# Sheet1.net
KiCad netlist of a schematic drawn in Altium Designer
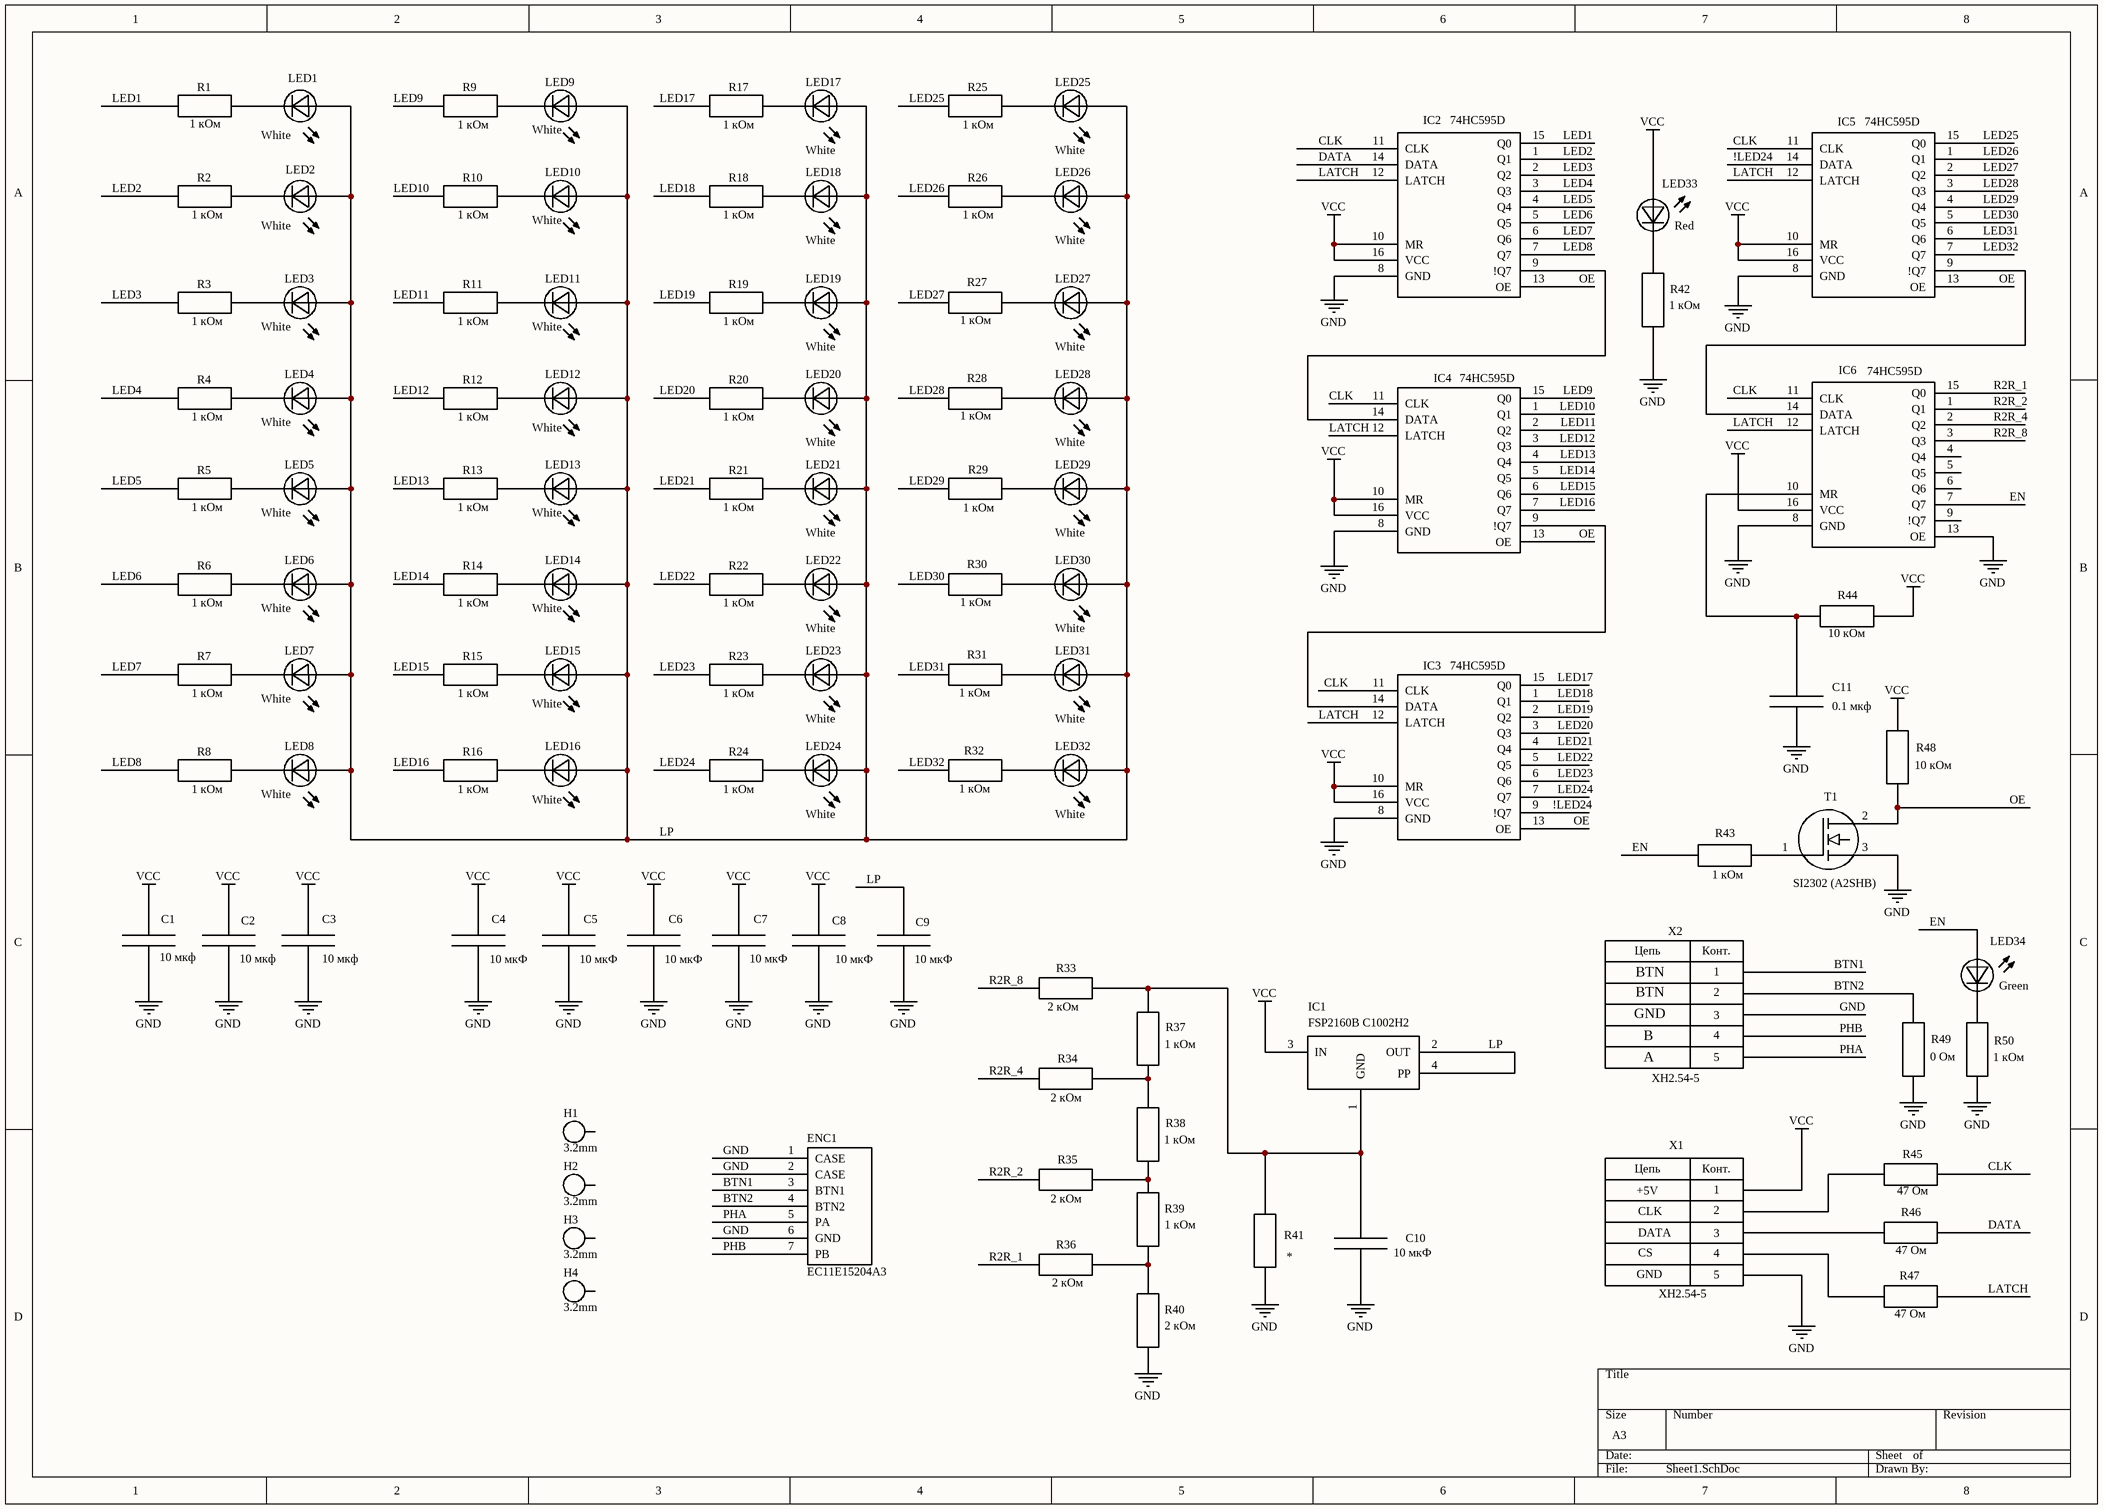
[diagram p0: Sheet1.SchDoc]

(export (version "E")
  (design (tool "Eeschema 10.0.6"))
  (components
    (comp (ref "C1")
      (value "10 мкф")
      (footprint "Конденсатор SMD Case 1206")
      (libsource (lib "S83") (part "Конденсатор"))
    )
    (comp (ref "C2")
      (value "10 мкф")
      (footprint "Конденсатор SMD Case 1206")
      (libsource (lib "S83") (part "Конденсатор"))
    )
    (comp (ref "C3")
      (value "10 мкф")
      (footprint "Конденсатор SMD Case 1206")
      (libsource (lib "S83") (part "Конденсатор"))
    )
    (comp (ref "C4")
      (value "10 мкФ")
      (footprint "Конденсатор SMD Case 1206")
      (libsource (lib "S83") (part "Конденсатор"))
    )
    (comp (ref "C5")
      (value "10 мкФ")
      (footprint "Конденсатор SMD Case 1206")
      (libsource (lib "S83") (part "Конденсатор"))
    )
    (comp (ref "C6")
      (value "10 мкФ")
      (footprint "Конденсатор SMD Case 1206")
      (libsource (lib "S83") (part "Конденсатор"))
    )
    (comp (ref "C7")
      (value "10 мкФ")
      (footprint "Конденсатор SMD Case 1206")
      (libsource (lib "S83") (part "Конденсатор"))
    )
    (comp (ref "C8")
      (value "10 мкФ")
      (footprint "Конденсатор SMD Case 1206")
      (libsource (lib "S83") (part "Конденсатор"))
    )
    (comp (ref "C9")
      (value "10 мкФ")
      (footprint "Конденсатор SMD Case 1206")
      (libsource (lib "S83") (part "Конденсатор"))
    )
    (comp (ref "C10")
      (value "10 мкФ")
      (footprint "Конденсатор SMD Case 1206")
      (libsource (lib "S83") (part "Конденсатор"))
    )
    (comp (ref "C11")
      (value "0.1 мкф")
      (footprint "Конденсатор SMD Case 1206")
      (libsource (lib "S83") (part "Конденсатор"))
    )
    (comp (ref "ENC1")
      (value "EC11E15204A3")
      (footprint "Encoder")
      (libsource (lib "S83") (part "Encoder_01"))
    )
    (comp (ref "H1")
      (value "3.2mm")
      (footprint "Отверстие 3,2")
      (libsource (lib "S83") (part "Отверстие монтажное"))
    )
    (comp (ref "H2")
      (value "3.2mm")
      (footprint "Отверстие 3,2")
      (libsource (lib "S83") (part "Отверстие монтажное"))
    )
    (comp (ref "H3")
      (value "3.2mm")
      (footprint "Отверстие 3,2")
      (libsource (lib "S83") (part "Отверстие монтажное"))
    )
    (comp (ref "H4")
      (value "3.2mm")
      (footprint "Отверстие 3,2")
      (libsource (lib "S83") (part "Отверстие монтажное"))
    )
    (comp (ref "IC1")
      (value "FSP2160B C1002H2")
      (footprint "SOT-223")
      (libsource (lib "S83_IC") (part "FSP2160B J1003H1"))
    )
    (comp (ref "IC2") (value "74HC595D") (footprint "SO-16") (libsource (lib "S83_IC") (part "74HC595D")))
    (comp (ref "IC3") (value "74HC595D") (footprint "SO-16") (libsource (lib "S83_IC") (part "74HC595D")))
    (comp (ref "IC4") (value "74HC595D") (footprint "SO-16") (libsource (lib "S83_IC") (part "74HC595D")))
    (comp (ref "IC5") (value "74HC595D") (footprint "SO-16") (libsource (lib "S83_IC") (part "74HC595D")))
    (comp (ref "IC6") (value "74HC595D") (footprint "SO-16") (libsource (lib "S83_IC") (part "74HC595D")))
    (comp (ref "LED1")
      (value "White")
      (footprint "Светодиод  5x2 mm")
      (libsource (lib "S83") (part "Светодиод"))
    )
    (comp (ref "LED2")
      (value "White")
      (footprint "Светодиод  5x2 mm")
      (libsource (lib "S83") (part "Светодиод"))
    )
    (comp (ref "LED3")
      (value "White")
      (footprint "Светодиод  5x2 mm")
      (libsource (lib "S83") (part "Светодиод"))
    )
    (comp (ref "LED4")
      (value "White")
      (footprint "Светодиод  5x2 mm")
      (libsource (lib "S83") (part "Светодиод"))
    )
    (comp (ref "LED5")
      (value "White")
      (footprint "Светодиод  5x2 mm")
      (libsource (lib "S83") (part "Светодиод"))
    )
    (comp (ref "LED6")
      (value "White")
      (footprint "Светодиод  5x2 mm")
      (libsource (lib "S83") (part "Светодиод"))
    )
    (comp (ref "LED7")
      (value "White")
      (footprint "Светодиод  5x2 mm")
      (libsource (lib "S83") (part "Светодиод"))
    )
    (comp (ref "LED8")
      (value "White")
      (footprint "Светодиод  5x2 mm")
      (libsource (lib "S83") (part "Светодиод"))
    )
    (comp (ref "LED9")
      (value "White")
      (footprint "Светодиод  5x2 mm")
      (libsource (lib "S83") (part "Светодиод"))
    )
    (comp (ref "LED10")
      (value "White")
      (footprint "Светодиод  5x2 mm")
      (libsource (lib "S83") (part "Светодиод"))
    )
    (comp (ref "LED11")
      (value "White")
      (footprint "Светодиод  5x2 mm")
      (libsource (lib "S83") (part "Светодиод"))
    )
    (comp (ref "LED12")
      (value "White")
      (footprint "Светодиод  5x2 mm")
      (libsource (lib "S83") (part "Светодиод"))
    )
    (comp (ref "LED13")
      (value "White")
      (footprint "Светодиод  5x2 mm")
      (libsource (lib "S83") (part "Светодиод"))
    )
    (comp (ref "LED14")
      (value "White")
      (footprint "Светодиод  5x2 mm")
      (libsource (lib "S83") (part "Светодиод"))
    )
    (comp (ref "LED15")
      (value "White")
      (footprint "Светодиод  5x2 mm")
      (libsource (lib "S83") (part "Светодиод"))
    )
    (comp (ref "LED16")
      (value "White")
      (footprint "Светодиод  5x2 mm")
      (libsource (lib "S83") (part "Светодиод"))
    )
    (comp (ref "LED17")
      (value "White")
      (footprint "Светодиод  5x2 mm")
      (libsource (lib "S83") (part "Светодиод"))
    )
    (comp (ref "LED18")
      (value "White")
      (footprint "Светодиод  5x2 mm")
      (libsource (lib "S83") (part "Светодиод"))
    )
    (comp (ref "LED19")
      (value "White")
      (footprint "Светодиод  5x2 mm")
      (libsource (lib "S83") (part "Светодиод"))
    )
    (comp (ref "LED20")
      (value "White")
      (footprint "Светодиод  5x2 mm")
      (libsource (lib "S83") (part "Светодиод"))
    )
    (comp (ref "LED21")
      (value "White")
      (footprint "Светодиод  5x2 mm")
      (libsource (lib "S83") (part "Светодиод"))
    )
    (comp (ref "LED22")
      (value "White")
      (footprint "Светодиод  5x2 mm")
      (libsource (lib "S83") (part "Светодиод"))
    )
    (comp (ref "LED23")
      (value "White")
      (footprint "Светодиод  5x2 mm")
      (libsource (lib "S83") (part "Светодиод"))
    )
    (comp (ref "LED24")
      (value "White")
      (footprint "Светодиод  5x2 mm")
      (libsource (lib "S83") (part "Светодиод"))
    )
    (comp (ref "LED25")
      (value "White")
      (footprint "Светодиод  5x2 mm")
      (libsource (lib "S83") (part "Светодиод"))
    )
    (comp (ref "LED26")
      (value "White")
      (footprint "Светодиод  5x2 mm")
      (libsource (lib "S83") (part "Светодиод"))
    )
    (comp (ref "LED27")
      (value "White")
      (footprint "Светодиод  5x2 mm")
      (libsource (lib "S83") (part "Светодиод"))
    )
    (comp (ref "LED28")
      (value "White")
      (footprint "Светодиод  5x2 mm")
      (libsource (lib "S83") (part "Светодиод"))
    )
    (comp (ref "LED29")
      (value "White")
      (footprint "Светодиод  5x2 mm")
      (libsource (lib "S83") (part "Светодиод"))
    )
    (comp (ref "LED30")
      (value "White")
      (footprint "Светодиод  5x2 mm")
      (libsource (lib "S83") (part "Светодиод"))
    )
    (comp (ref "LED31")
      (value "White")
      (footprint "Светодиод  5x2 mm")
      (libsource (lib "S83") (part "Светодиод"))
    )
    (comp (ref "LED32")
      (value "White")
      (footprint "Светодиод  5x2 mm")
      (libsource (lib "S83") (part "Светодиод"))
    )
    (comp (ref "LED33")
      (value "Red")
      (footprint "SMD 1206 Светодиод ВАЙТ")
      (libsource (lib "S83") (part "Светодиод"))
    )
    (comp (ref "LED34")
      (value "Green")
      (footprint "SMD 1206 Светодиод ВАЙТ")
      (libsource (lib "S83") (part "Светодиод"))
    )
    (comp (ref "R1")
      (value "1 кОм")
      (footprint "SMD 0805 Резистор")
      (libsource (lib "S83") (part "Резистор"))
    )
    (comp (ref "R2")
      (value "1 кОм")
      (footprint "SMD 0805 Резистор")
      (libsource (lib "S83") (part "Резистор"))
    )
    (comp (ref "R3")
      (value "1 кОм")
      (footprint "SMD 0805 Резистор")
      (libsource (lib "S83") (part "Резистор"))
    )
    (comp (ref "R4")
      (value "1 кОм")
      (footprint "SMD 0805 Резистор")
      (libsource (lib "S83") (part "Резистор"))
    )
    (comp (ref "R5")
      (value "1 кОм")
      (footprint "SMD 0805 Резистор")
      (libsource (lib "S83") (part "Резистор"))
    )
    (comp (ref "R6")
      (value "1 кОм")
      (footprint "SMD 0805 Резистор")
      (libsource (lib "S83") (part "Резистор"))
    )
    (comp (ref "R7")
      (value "1 кОм")
      (footprint "SMD 0805 Резистор")
      (libsource (lib "S83") (part "Резистор"))
    )
    (comp (ref "R8")
      (value "1 кОм")
      (footprint "SMD 0805 Резистор")
      (libsource (lib "S83") (part "Резистор"))
    )
    (comp (ref "R9")
      (value "1 кОм")
      (footprint "SMD 0805 Резистор")
      (libsource (lib "S83") (part "Резистор"))
    )
    (comp (ref "R10")
      (value "1 кОм")
      (footprint "SMD 0805 Резистор")
      (libsource (lib "S83") (part "Резистор"))
    )
    (comp (ref "R11")
      (value "1 кОм")
      (footprint "SMD 0805 Резистор")
      (libsource (lib "S83") (part "Резистор"))
    )
    (comp (ref "R12")
      (value "1 кОм")
      (footprint "SMD 0805 Резистор")
      (libsource (lib "S83") (part "Резистор"))
    )
    (comp (ref "R13")
      (value "1 кОм")
      (footprint "SMD 0805 Резистор")
      (libsource (lib "S83") (part "Резистор"))
    )
    (comp (ref "R14")
      (value "1 кОм")
      (footprint "SMD 0805 Резистор")
      (libsource (lib "S83") (part "Резистор"))
    )
    (comp (ref "R15")
      (value "1 кОм")
      (footprint "SMD 0805 Резистор")
      (libsource (lib "S83") (part "Резистор"))
    )
    (comp (ref "R16")
      (value "1 кОм")
      (footprint "SMD 0805 Резистор")
      (libsource (lib "S83") (part "Резистор"))
    )
    (comp (ref "R17")
      (value "1 кОм")
      (footprint "SMD 0805 Резистор")
      (libsource (lib "S83") (part "Резистор"))
    )
    (comp (ref "R18")
      (value "1 кОм")
      (footprint "SMD 0805 Резистор")
      (libsource (lib "S83") (part "Резистор"))
    )
    (comp (ref "R19")
      (value "1 кОм")
      (footprint "SMD 0805 Резистор")
      (libsource (lib "S83") (part "Резистор"))
    )
    (comp (ref "R20")
      (value "1 кОм")
      (footprint "SMD 0805 Резистор")
      (libsource (lib "S83") (part "Резистор"))
    )
    (comp (ref "R21")
      (value "1 кОм")
      (footprint "SMD 0805 Резистор")
      (libsource (lib "S83") (part "Резистор"))
    )
    (comp (ref "R22")
      (value "1 кОм")
      (footprint "SMD 0805 Резистор")
      (libsource (lib "S83") (part "Резистор"))
    )
    (comp (ref "R23")
      (value "1 кОм")
      (footprint "SMD 0805 Резистор")
      (libsource (lib "S83") (part "Резистор"))
    )
    (comp (ref "R24")
      (value "1 кОм")
      (footprint "SMD 0805 Резистор")
      (libsource (lib "S83") (part "Резистор"))
    )
    (comp (ref "R25")
      (value "1 кОм")
      (footprint "SMD 0805 Резистор")
      (libsource (lib "S83") (part "Резистор"))
    )
    (comp (ref "R26")
      (value "1 кОм")
      (footprint "SMD 0805 Резистор")
      (libsource (lib "S83") (part "Резистор"))
    )
    (comp (ref "R27")
      (value "1 кОм")
      (footprint "SMD 0805 Резистор")
      (libsource (lib "S83") (part "Резистор"))
    )
    (comp (ref "R28")
      (value "1 кОм")
      (footprint "SMD 0805 Резистор")
      (libsource (lib "S83") (part "Резистор"))
    )
    (comp (ref "R29")
      (value "1 кОм")
      (footprint "SMD 0805 Резистор")
      (libsource (lib "S83") (part "Резистор"))
    )
    (comp (ref "R30")
      (value "1 кОм")
      (footprint "SMD 0805 Резистор")
      (libsource (lib "S83") (part "Резистор"))
    )
    (comp (ref "R31")
      (value "1 кОм")
      (footprint "SMD 0805 Резистор")
      (libsource (lib "S83") (part "Резистор"))
    )
    (comp (ref "R32")
      (value "1 кОм")
      (footprint "SMD 0805 Резистор")
      (libsource (lib "S83") (part "Резистор"))
    )
    (comp (ref "R33")
      (value "2 кОм")
      (footprint "SMD 0805 Резистор")
      (libsource (lib "S83") (part "Резистор"))
    )
    (comp (ref "R34")
      (value "2 кОм")
      (footprint "SMD 0805 Резистор")
      (libsource (lib "S83") (part "Резистор"))
    )
    (comp (ref "R35")
      (value "2 кОм")
      (footprint "SMD 0805 Резистор")
      (libsource (lib "S83") (part "Резистор"))
    )
    (comp (ref "R36")
      (value "2 кОм")
      (footprint "SMD 0805 Резистор")
      (libsource (lib "S83") (part "Резистор"))
    )
    (comp (ref "R37")
      (value "1 кОм")
      (footprint "SMD 0805 Резистор")
      (libsource (lib "S83") (part "Резистор"))
    )
    (comp (ref "R38")
      (value "1 кОм")
      (footprint "SMD 0805 Резистор")
      (libsource (lib "S83") (part "Резистор"))
    )
    (comp (ref "R39")
      (value "1 кОм")
      (footprint "SMD 0805 Резистор")
      (libsource (lib "S83") (part "Резистор"))
    )
    (comp (ref "R40")
      (value "2 кОм")
      (footprint "SMD 0805 Резистор")
      (libsource (lib "S83") (part "Резистор"))
    )
    (comp (ref "R41") (value "*") (footprint "SMD 0805 Резистор") (libsource (lib "S83") (part "Резистор")))
    (comp (ref "R42")
      (value "1 кОм")
      (footprint "SMD 0805 Резистор")
      (libsource (lib "S83") (part "Резистор"))
    )
    (comp (ref "R43")
      (value "1 кОм")
      (footprint "SMD 0805 Резистор")
      (libsource (lib "S83") (part "Резистор"))
    )
    (comp (ref "R44")
      (value "10 кОм")
      (footprint "SMD 0805 Резистор")
      (libsource (lib "S83") (part "Резистор"))
    )
    (comp (ref "R45")
      (value "47 Ом")
      (footprint "SMD 0805 Резистор")
      (libsource (lib "S83") (part "Резистор"))
    )
    (comp (ref "R46")
      (value "47 Ом")
      (footprint "SMD 0805 Резистор")
      (libsource (lib "S83") (part "Резистор"))
    )
    (comp (ref "R47")
      (value "47 Ом")
      (footprint "SMD 0805 Резистор")
      (libsource (lib "S83") (part "Резистор"))
    )
    (comp (ref "R48")
      (value "10 кОм")
      (footprint "SMD 0805 Резистор")
      (libsource (lib "S83") (part "Резистор"))
    )
    (comp (ref "R49")
      (value "0 Ом")
      (footprint "SMD 0805 Резистор")
      (libsource (lib "S83") (part "Резистор"))
    )
    (comp (ref "R50")
      (value "1 кОм")
      (footprint "SMD 0805 Резистор")
      (libsource (lib "S83") (part "Резистор"))
    )
    (comp (ref "T1")
      (value "SI2302 (A2SHB)")
      (footprint "SMD SOT-23 Транзистор 3 pin")
      (libsource (lib "S83") (part "Транзистор MOSFET N-конал (как n-p-n)"))
    )
    (comp (ref "X1")
      (value "XH2.54-5")
      (footprint "(1x5)pin XH 2.54 Header")
      (libsource (lib "S83_connectors") (part "(1x5) pin 2.54 Header"))
    )
    (comp (ref "X2")
      (value "XH2.54-5")
      (footprint "(1x5)pin XH 2.54 Header")
      (libsource (lib "S83_connectors") (part "(1x5) pin 2.54 Header"))
    )
  )
  (nets
    (net (code "1") (name "/!LED24") (class "Default")
      (node (ref "IC3") (pin "9") (pinfunction "!Q7_9") (pintype "passive"))
      (node (ref "IC5") (pin "14") (pinfunction "DATA_14") (pintype "passive"))
    )
    (net (code "2") (name "/BTN1") (class "Default")
      (node (ref "ENC1") (pin "3") (pinfunction "BTN1_3") (pintype "passive"))
      (node (ref "X2") (pin "1") (pinfunction "1_1") (pintype "passive"))
    )
    (net (code "3") (name "/BTN2") (class "Default")
      (node (ref "ENC1") (pin "4") (pinfunction "BTN2_4") (pintype "passive"))
      (node (ref "R49") (pin "2") (pinfunction "right_2") (pintype "passive"))
      (node (ref "X2") (pin "2") (pinfunction "2_2") (pintype "passive"))
    )
    (net (code "4") (name "/CLK") (class "Default")
      (node (ref "IC2") (pin "11") (pinfunction "CLK_11") (pintype "passive"))
      (node (ref "IC3") (pin "11") (pinfunction "CLK_11") (pintype "passive"))
      (node (ref "IC4") (pin "11") (pinfunction "CLK_11") (pintype "passive"))
      (node (ref "IC5") (pin "11") (pinfunction "CLK_11") (pintype "passive"))
      (node (ref "IC6") (pin "11") (pinfunction "CLK_11") (pintype "passive"))
      (node (ref "R45") (pin "1") (pinfunction "left_1") (pintype "passive"))
    )
    (net (code "5") (name "/DATA") (class "Default")
      (node (ref "IC2") (pin "14") (pinfunction "DATA_14") (pintype "passive"))
      (node (ref "R46") (pin "1") (pinfunction "left_1") (pintype "passive"))
    )
    (net (code "6") (name "/EN") (class "Default")
      (node (ref "IC6") (pin "7") (pinfunction "Q7_7") (pintype "passive"))
      (node (ref "LED34") (pin "1") (pinfunction "А_1") (pintype "passive"))
      (node (ref "R43") (pin "2") (pinfunction "right_2") (pintype "passive"))
    )
    (net (code "7") (name "/LATCH") (class "Default")
      (node (ref "IC2") (pin "12") (pinfunction "LATCH_12") (pintype "passive"))
      (node (ref "IC3") (pin "12") (pinfunction "LATCH_12") (pintype "passive"))
      (node (ref "IC4") (pin "12") (pinfunction "LATCH_12") (pintype "passive"))
      (node (ref "IC5") (pin "12") (pinfunction "LATCH_12") (pintype "passive"))
      (node (ref "IC6") (pin "12") (pinfunction "LATCH_12") (pintype "passive"))
      (node (ref "R47") (pin "1") (pinfunction "left_1") (pintype "passive"))
    )
    (net (code "8") (name "/LED1") (class "Default")
      (node (ref "IC2") (pin "15") (pinfunction "Q0_15") (pintype "passive"))
      (node (ref "R1") (pin "1") (pinfunction "left_1") (pintype "passive"))
    )
    (net (code "9") (name "/LED2") (class "Default")
      (node (ref "IC2") (pin "1") (pinfunction "Q1_1") (pintype "passive"))
      (node (ref "R2") (pin "1") (pinfunction "left_1") (pintype "passive"))
    )
    (net (code "10") (name "/LED3") (class "Default")
      (node (ref "IC2") (pin "2") (pinfunction "Q2_2") (pintype "passive"))
      (node (ref "R3") (pin "1") (pinfunction "left_1") (pintype "passive"))
    )
    (net (code "11") (name "/LED4") (class "Default")
      (node (ref "IC2") (pin "3") (pinfunction "Q3_3") (pintype "passive"))
      (node (ref "R4") (pin "1") (pinfunction "left_1") (pintype "passive"))
    )
    (net (code "12") (name "/LED5") (class "Default")
      (node (ref "IC2") (pin "4") (pinfunction "Q4_4") (pintype "passive"))
      (node (ref "R5") (pin "1") (pinfunction "left_1") (pintype "passive"))
    )
    (net (code "13") (name "/LED6") (class "Default")
      (node (ref "IC2") (pin "5") (pinfunction "Q5_5") (pintype "passive"))
      (node (ref "R6") (pin "1") (pinfunction "left_1") (pintype "passive"))
    )
    (net (code "14") (name "/LED7") (class "Default")
      (node (ref "IC2") (pin "6") (pinfunction "Q6_6") (pintype "passive"))
      (node (ref "R7") (pin "1") (pinfunction "left_1") (pintype "passive"))
    )
    (net (code "15") (name "/LED8") (class "Default")
      (node (ref "IC2") (pin "7") (pinfunction "Q7_7") (pintype "passive"))
      (node (ref "R8") (pin "1") (pinfunction "left_1") (pintype "passive"))
    )
    (net (code "16") (name "/LED9") (class "Default")
      (node (ref "IC4") (pin "15") (pinfunction "Q0_15") (pintype "passive"))
      (node (ref "R9") (pin "1") (pinfunction "left_1") (pintype "passive"))
    )
    (net (code "17") (name "/LED10") (class "Default")
      (node (ref "IC4") (pin "1") (pinfunction "Q1_1") (pintype "passive"))
      (node (ref "R10") (pin "1") (pinfunction "left_1") (pintype "passive"))
    )
    (net (code "18") (name "/LED11") (class "Default")
      (node (ref "IC4") (pin "2") (pinfunction "Q2_2") (pintype "passive"))
      (node (ref "R11") (pin "1") (pinfunction "left_1") (pintype "passive"))
    )
    (net (code "19") (name "/LED12") (class "Default")
      (node (ref "IC4") (pin "3") (pinfunction "Q3_3") (pintype "passive"))
      (node (ref "R12") (pin "1") (pinfunction "left_1") (pintype "passive"))
    )
    (net (code "20") (name "/LED13") (class "Default")
      (node (ref "IC4") (pin "4") (pinfunction "Q4_4") (pintype "passive"))
      (node (ref "R13") (pin "1") (pinfunction "left_1") (pintype "passive"))
    )
    (net (code "21") (name "/LED14") (class "Default")
      (node (ref "IC4") (pin "5") (pinfunction "Q5_5") (pintype "passive"))
      (node (ref "R14") (pin "1") (pinfunction "left_1") (pintype "passive"))
    )
    (net (code "22") (name "/LED15") (class "Default")
      (node (ref "IC4") (pin "6") (pinfunction "Q6_6") (pintype "passive"))
      (node (ref "R15") (pin "1") (pinfunction "left_1") (pintype "passive"))
    )
    (net (code "23") (name "/LED16") (class "Default")
      (node (ref "IC4") (pin "7") (pinfunction "Q7_7") (pintype "passive"))
      (node (ref "R16") (pin "1") (pinfunction "left_1") (pintype "passive"))
    )
    (net (code "24") (name "/LED17") (class "Default")
      (node (ref "IC3") (pin "15") (pinfunction "Q0_15") (pintype "passive"))
      (node (ref "R17") (pin "1") (pinfunction "left_1") (pintype "passive"))
    )
    (net (code "25") (name "/LED18") (class "Default")
      (node (ref "IC3") (pin "1") (pinfunction "Q1_1") (pintype "passive"))
      (node (ref "R18") (pin "1") (pinfunction "left_1") (pintype "passive"))
    )
    (net (code "26") (name "/LED19") (class "Default")
      (node (ref "IC3") (pin "2") (pinfunction "Q2_2") (pintype "passive"))
      (node (ref "R19") (pin "1") (pinfunction "left_1") (pintype "passive"))
    )
    (net (code "27") (name "/LED20") (class "Default")
      (node (ref "IC3") (pin "3") (pinfunction "Q3_3") (pintype "passive"))
      (node (ref "R20") (pin "1") (pinfunction "left_1") (pintype "passive"))
    )
    (net (code "28") (name "/LED21") (class "Default")
      (node (ref "IC3") (pin "4") (pinfunction "Q4_4") (pintype "passive"))
      (node (ref "R21") (pin "1") (pinfunction "left_1") (pintype "passive"))
    )
    (net (code "29") (name "/LED22") (class "Default")
      (node (ref "IC3") (pin "5") (pinfunction "Q5_5") (pintype "passive"))
      (node (ref "R22") (pin "1") (pinfunction "left_1") (pintype "passive"))
    )
    (net (code "30") (name "/LED23") (class "Default")
      (node (ref "IC3") (pin "6") (pinfunction "Q6_6") (pintype "passive"))
      (node (ref "R23") (pin "1") (pinfunction "left_1") (pintype "passive"))
    )
    (net (code "31") (name "/LED24") (class "Default")
      (node (ref "IC3") (pin "7") (pinfunction "Q7_7") (pintype "passive"))
      (node (ref "R24") (pin "1") (pinfunction "left_1") (pintype "passive"))
    )
    (net (code "32") (name "/LED25") (class "Default")
      (node (ref "IC5") (pin "15") (pinfunction "Q0_15") (pintype "passive"))
      (node (ref "R25") (pin "1") (pinfunction "left_1") (pintype "passive"))
    )
    (net (code "33") (name "/LED26") (class "Default")
      (node (ref "IC5") (pin "1") (pinfunction "Q1_1") (pintype "passive"))
      (node (ref "R26") (pin "1") (pinfunction "left_1") (pintype "passive"))
    )
    (net (code "34") (name "/LED27") (class "Default")
      (node (ref "IC5") (pin "2") (pinfunction "Q2_2") (pintype "passive"))
      (node (ref "R27") (pin "1") (pinfunction "left_1") (pintype "passive"))
    )
    (net (code "35") (name "/LED28") (class "Default")
      (node (ref "IC5") (pin "3") (pinfunction "Q3_3") (pintype "passive"))
      (node (ref "R28") (pin "1") (pinfunction "left_1") (pintype "passive"))
    )
    (net (code "36") (name "/LED29") (class "Default")
      (node (ref "IC5") (pin "4") (pinfunction "Q4_4") (pintype "passive"))
      (node (ref "R29") (pin "1") (pinfunction "left_1") (pintype "passive"))
    )
    (net (code "37") (name "/LED30") (class "Default")
      (node (ref "IC5") (pin "5") (pinfunction "Q5_5") (pintype "passive"))
      (node (ref "R30") (pin "1") (pinfunction "left_1") (pintype "passive"))
    )
    (net (code "38") (name "/LED31") (class "Default")
      (node (ref "IC5") (pin "6") (pinfunction "Q6_6") (pintype "passive"))
      (node (ref "R31") (pin "1") (pinfunction "left_1") (pintype "passive"))
    )
    (net (code "39") (name "/LED32") (class "Default")
      (node (ref "IC5") (pin "7") (pinfunction "Q7_7") (pintype "passive"))
      (node (ref "R32") (pin "1") (pinfunction "left_1") (pintype "passive"))
    )
    (net (code "40") (name "/LP") (class "Default")
      (node (ref "C9") (pin "1") (pinfunction "+_1") (pintype "passive"))
      (node (ref "IC1") (pin "2") (pinfunction "OUT_2") (pintype "passive"))
      (node (ref "IC1") (pin "4") (pinfunction "PP_4") (pintype "passive"))
      (node (ref "LED1") (pin "1") (pinfunction "А_1") (pintype "passive"))
      (node (ref "LED10") (pin "1") (pinfunction "А_1") (pintype "passive"))
      (node (ref "LED11") (pin "1") (pinfunction "А_1") (pintype "passive"))
      (node (ref "LED12") (pin "1") (pinfunction "А_1") (pintype "passive"))
      (node (ref "LED13") (pin "1") (pinfunction "А_1") (pintype "passive"))
      (node (ref "LED14") (pin "1") (pinfunction "А_1") (pintype "passive"))
      (node (ref "LED15") (pin "1") (pinfunction "А_1") (pintype "passive"))
      (node (ref "LED16") (pin "1") (pinfunction "А_1") (pintype "passive"))
      (node (ref "LED17") (pin "1") (pinfunction "А_1") (pintype "passive"))
      (node (ref "LED18") (pin "1") (pinfunction "А_1") (pintype "passive"))
      (node (ref "LED19") (pin "1") (pinfunction "А_1") (pintype "passive"))
      (node (ref "LED2") (pin "1") (pinfunction "А_1") (pintype "passive"))
      (node (ref "LED20") (pin "1") (pinfunction "А_1") (pintype "passive"))
      (node (ref "LED21") (pin "1") (pinfunction "А_1") (pintype "passive"))
      (node (ref "LED22") (pin "1") (pinfunction "А_1") (pintype "passive"))
      (node (ref "LED23") (pin "1") (pinfunction "А_1") (pintype "passive"))
      (node (ref "LED24") (pin "1") (pinfunction "А_1") (pintype "passive"))
      (node (ref "LED25") (pin "1") (pinfunction "А_1") (pintype "passive"))
      (node (ref "LED26") (pin "1") (pinfunction "А_1") (pintype "passive"))
      (node (ref "LED27") (pin "1") (pinfunction "А_1") (pintype "passive"))
      (node (ref "LED28") (pin "1") (pinfunction "А_1") (pintype "passive"))
      (node (ref "LED29") (pin "1") (pinfunction "А_1") (pintype "passive"))
      (node (ref "LED3") (pin "1") (pinfunction "А_1") (pintype "passive"))
      (node (ref "LED30") (pin "1") (pinfunction "А_1") (pintype "passive"))
      (node (ref "LED31") (pin "1") (pinfunction "А_1") (pintype "passive"))
      (node (ref "LED32") (pin "1") (pinfunction "А_1") (pintype "passive"))
      (node (ref "LED4") (pin "1") (pinfunction "А_1") (pintype "passive"))
      (node (ref "LED5") (pin "1") (pinfunction "А_1") (pintype "passive"))
      (node (ref "LED6") (pin "1") (pinfunction "А_1") (pintype "passive"))
      (node (ref "LED7") (pin "1") (pinfunction "А_1") (pintype "passive"))
      (node (ref "LED8") (pin "1") (pinfunction "А_1") (pintype "passive"))
      (node (ref "LED9") (pin "1") (pinfunction "А_1") (pintype "passive"))
    )
    (net (code "41") (name "/OE") (class "Default")
      (node (ref "IC2") (pin "13") (pinfunction "OE_13") (pintype "passive"))
      (node (ref "IC3") (pin "13") (pinfunction "OE_13") (pintype "passive"))
      (node (ref "IC4") (pin "13") (pinfunction "OE_13") (pintype "passive"))
      (node (ref "IC5") (pin "13") (pinfunction "OE_13") (pintype "passive"))
      (node (ref "R48") (pin "2") (pinfunction "right_2") (pintype "passive"))
      (node (ref "T1") (pin "2") (pinfunction "2_2") (pintype "passive"))
    )
    (net (code "42") (name "/PHA") (class "Default")
      (node (ref "ENC1") (pin "5") (pinfunction "PA_5") (pintype "passive"))
      (node (ref "X2") (pin "5") (pinfunction "5_5") (pintype "passive"))
    )
    (net (code "43") (name "/PHB") (class "Default")
      (node (ref "ENC1") (pin "7") (pinfunction "PB_7") (pintype "passive"))
      (node (ref "X2") (pin "4") (pinfunction "4_4") (pintype "passive"))
    )
    (net (code "44") (name "/R2R_1") (class "Default")
      (node (ref "IC6") (pin "15") (pinfunction "Q0_15") (pintype "passive"))
      (node (ref "R36") (pin "1") (pinfunction "left_1") (pintype "passive"))
    )
    (net (code "45") (name "/R2R_2") (class "Default")
      (node (ref "IC6") (pin "1") (pinfunction "Q1_1") (pintype "passive"))
      (node (ref "R35") (pin "1") (pinfunction "left_1") (pintype "passive"))
    )
    (net (code "46") (name "/R2R_4") (class "Default")
      (node (ref "IC6") (pin "2") (pinfunction "Q2_2") (pintype "passive"))
      (node (ref "R34") (pin "1") (pinfunction "left_1") (pintype "passive"))
    )
    (net (code "47") (name "/R2R_8") (class "Default")
      (node (ref "IC6") (pin "3") (pinfunction "Q3_3") (pintype "passive"))
      (node (ref "R33") (pin "1") (pinfunction "left_1") (pintype "passive"))
    )
    (net (code "48") (name "GND") (class "Default")
      (node (ref "C1") (pin "2") (pinfunction "-_2") (pintype "passive"))
      (node (ref "C10") (pin "2") (pinfunction "-_2") (pintype "passive"))
      (node (ref "C11") (pin "2") (pinfunction "-_2") (pintype "passive"))
      (node (ref "C2") (pin "2") (pinfunction "-_2") (pintype "passive"))
      (node (ref "C3") (pin "2") (pinfunction "-_2") (pintype "passive"))
      (node (ref "C4") (pin "2") (pinfunction "-_2") (pintype "passive"))
      (node (ref "C5") (pin "2") (pinfunction "-_2") (pintype "passive"))
      (node (ref "C6") (pin "2") (pinfunction "-_2") (pintype "passive"))
      (node (ref "C7") (pin "2") (pinfunction "-_2") (pintype "passive"))
      (node (ref "C8") (pin "2") (pinfunction "-_2") (pintype "passive"))
      (node (ref "C9") (pin "2") (pinfunction "-_2") (pintype "passive"))
      (node (ref "ENC1") (pin "1") (pinfunction "CASE_1") (pintype "passive"))
      (node (ref "ENC1") (pin "2") (pinfunction "CASE_2") (pintype "passive"))
      (node (ref "ENC1") (pin "6") (pinfunction "GND_6") (pintype "passive"))
      (node (ref "IC2") (pin "8") (pinfunction "GND_8") (pintype "passive"))
      (node (ref "IC3") (pin "8") (pinfunction "GND_8") (pintype "passive"))
      (node (ref "IC4") (pin "8") (pinfunction "GND_8") (pintype "passive"))
      (node (ref "IC5") (pin "8") (pinfunction "GND_8") (pintype "passive"))
      (node (ref "IC6") (pin "13") (pinfunction "OE_13") (pintype "passive"))
      (node (ref "IC6") (pin "8") (pinfunction "GND_8") (pintype "passive"))
      (node (ref "R40") (pin "1") (pinfunction "left_1") (pintype "passive"))
      (node (ref "R41") (pin "1") (pinfunction "left_1") (pintype "passive"))
      (node (ref "R42") (pin "1") (pinfunction "left_1") (pintype "passive"))
      (node (ref "R49") (pin "1") (pinfunction "left_1") (pintype "passive"))
      (node (ref "R50") (pin "1") (pinfunction "left_1") (pintype "passive"))
      (node (ref "T1") (pin "3") (pinfunction "3_3") (pintype "passive"))
      (node (ref "X1") (pin "5") (pinfunction "5_5") (pintype "passive"))
      (node (ref "X2") (pin "3") (pinfunction "3_3") (pintype "passive"))
    )
    (net (code "49") (name "Net-(C10-+)") (class "Default")
      (node (ref "C10") (pin "1") (pinfunction "+_1") (pintype "passive"))
      (node (ref "IC1") (pin "1") (pinfunction "GND_1") (pintype "passive"))
      (node (ref "R33") (pin "2") (pinfunction "right_2") (pintype "passive"))
      (node (ref "R37") (pin "2") (pinfunction "right_2") (pintype "passive"))
      (node (ref "R41") (pin "2") (pinfunction "right_2") (pintype "passive"))
    )
    (net (code "50") (name "Net-(C11-+)") (class "Default")
      (node (ref "C11") (pin "1") (pinfunction "+_1") (pintype "passive"))
      (node (ref "IC6") (pin "10") (pinfunction "MR_10") (pintype "passive"))
      (node (ref "R44") (pin "2") (pinfunction "right_2") (pintype "passive"))
    )
    (net (code "51") (name "Net-(IC2-!Q7)") (class "Default")
      (node (ref "IC2") (pin "9") (pinfunction "!Q7_9") (pintype "passive"))
      (node (ref "IC4") (pin "14") (pinfunction "DATA_14") (pintype "passive"))
    )
    (net (code "52") (name "Net-(IC3-DATA)") (class "Default")
      (node (ref "IC3") (pin "14") (pinfunction "DATA_14") (pintype "passive"))
      (node (ref "IC4") (pin "9") (pinfunction "!Q7_9") (pintype "passive"))
    )
    (net (code "53") (name "Net-(IC5-!Q7)") (class "Default")
      (node (ref "IC5") (pin "9") (pinfunction "!Q7_9") (pintype "passive"))
      (node (ref "IC6") (pin "14") (pinfunction "DATA_14") (pintype "passive"))
    )
    (net (code "54") (name "Net-(LED1-K)") (class "Default")
      (node (ref "LED1") (pin "2") (pinfunction "K_2") (pintype "passive"))
      (node (ref "R1") (pin "2") (pinfunction "right_2") (pintype "passive"))
    )
    (net (code "55") (name "Net-(LED2-K)") (class "Default")
      (node (ref "LED2") (pin "2") (pinfunction "K_2") (pintype "passive"))
      (node (ref "R2") (pin "2") (pinfunction "right_2") (pintype "passive"))
    )
    (net (code "56") (name "Net-(LED3-K)") (class "Default")
      (node (ref "LED3") (pin "2") (pinfunction "K_2") (pintype "passive"))
      (node (ref "R3") (pin "2") (pinfunction "right_2") (pintype "passive"))
    )
    (net (code "57") (name "Net-(LED4-K)") (class "Default")
      (node (ref "LED4") (pin "2") (pinfunction "K_2") (pintype "passive"))
      (node (ref "R4") (pin "2") (pinfunction "right_2") (pintype "passive"))
    )
    (net (code "58") (name "Net-(LED5-K)") (class "Default")
      (node (ref "LED5") (pin "2") (pinfunction "K_2") (pintype "passive"))
      (node (ref "R5") (pin "2") (pinfunction "right_2") (pintype "passive"))
    )
    (net (code "59") (name "Net-(LED6-K)") (class "Default")
      (node (ref "LED6") (pin "2") (pinfunction "K_2") (pintype "passive"))
      (node (ref "R6") (pin "2") (pinfunction "right_2") (pintype "passive"))
    )
    (net (code "60") (name "Net-(LED7-K)") (class "Default")
      (node (ref "LED7") (pin "2") (pinfunction "K_2") (pintype "passive"))
      (node (ref "R7") (pin "2") (pinfunction "right_2") (pintype "passive"))
    )
    (net (code "61") (name "Net-(LED8-K)") (class "Default")
      (node (ref "LED8") (pin "2") (pinfunction "K_2") (pintype "passive"))
      (node (ref "R8") (pin "2") (pinfunction "right_2") (pintype "passive"))
    )
    (net (code "62") (name "Net-(LED9-K)") (class "Default")
      (node (ref "LED9") (pin "2") (pinfunction "K_2") (pintype "passive"))
      (node (ref "R9") (pin "2") (pinfunction "right_2") (pintype "passive"))
    )
    (net (code "63") (name "Net-(LED10-K)") (class "Default")
      (node (ref "LED10") (pin "2") (pinfunction "K_2") (pintype "passive"))
      (node (ref "R10") (pin "2") (pinfunction "right_2") (pintype "passive"))
    )
    (net (code "64") (name "Net-(LED11-K)") (class "Default")
      (node (ref "LED11") (pin "2") (pinfunction "K_2") (pintype "passive"))
      (node (ref "R11") (pin "2") (pinfunction "right_2") (pintype "passive"))
    )
    (net (code "65") (name "Net-(LED12-K)") (class "Default")
      (node (ref "LED12") (pin "2") (pinfunction "K_2") (pintype "passive"))
      (node (ref "R12") (pin "2") (pinfunction "right_2") (pintype "passive"))
    )
    (net (code "66") (name "Net-(LED13-K)") (class "Default")
      (node (ref "LED13") (pin "2") (pinfunction "K_2") (pintype "passive"))
      (node (ref "R13") (pin "2") (pinfunction "right_2") (pintype "passive"))
    )
    (net (code "67") (name "Net-(LED14-K)") (class "Default")
      (node (ref "LED14") (pin "2") (pinfunction "K_2") (pintype "passive"))
      (node (ref "R14") (pin "2") (pinfunction "right_2") (pintype "passive"))
    )
    (net (code "68") (name "Net-(LED15-K)") (class "Default")
      (node (ref "LED15") (pin "2") (pinfunction "K_2") (pintype "passive"))
      (node (ref "R15") (pin "2") (pinfunction "right_2") (pintype "passive"))
    )
    (net (code "69") (name "Net-(LED16-K)") (class "Default")
      (node (ref "LED16") (pin "2") (pinfunction "K_2") (pintype "passive"))
      (node (ref "R16") (pin "2") (pinfunction "right_2") (pintype "passive"))
    )
    (net (code "70") (name "Net-(LED17-K)") (class "Default")
      (node (ref "LED17") (pin "2") (pinfunction "K_2") (pintype "passive"))
      (node (ref "R17") (pin "2") (pinfunction "right_2") (pintype "passive"))
    )
    (net (code "71") (name "Net-(LED18-K)") (class "Default")
      (node (ref "LED18") (pin "2") (pinfunction "K_2") (pintype "passive"))
      (node (ref "R18") (pin "2") (pinfunction "right_2") (pintype "passive"))
    )
    (net (code "72") (name "Net-(LED19-K)") (class "Default")
      (node (ref "LED19") (pin "2") (pinfunction "K_2") (pintype "passive"))
      (node (ref "R19") (pin "2") (pinfunction "right_2") (pintype "passive"))
    )
    (net (code "73") (name "Net-(LED20-K)") (class "Default")
      (node (ref "LED20") (pin "2") (pinfunction "K_2") (pintype "passive"))
      (node (ref "R20") (pin "2") (pinfunction "right_2") (pintype "passive"))
    )
    (net (code "74") (name "Net-(LED21-K)") (class "Default")
      (node (ref "LED21") (pin "2") (pinfunction "K_2") (pintype "passive"))
      (node (ref "R21") (pin "2") (pinfunction "right_2") (pintype "passive"))
    )
    (net (code "75") (name "Net-(LED22-K)") (class "Default")
      (node (ref "LED22") (pin "2") (pinfunction "K_2") (pintype "passive"))
      (node (ref "R22") (pin "2") (pinfunction "right_2") (pintype "passive"))
    )
    (net (code "76") (name "Net-(LED23-K)") (class "Default")
      (node (ref "LED23") (pin "2") (pinfunction "K_2") (pintype "passive"))
      (node (ref "R23") (pin "2") (pinfunction "right_2") (pintype "passive"))
    )
    (net (code "77") (name "Net-(LED24-K)") (class "Default")
      (node (ref "LED24") (pin "2") (pinfunction "K_2") (pintype "passive"))
      (node (ref "R24") (pin "2") (pinfunction "right_2") (pintype "passive"))
    )
    (net (code "78") (name "Net-(LED25-K)") (class "Default")
      (node (ref "LED25") (pin "2") (pinfunction "K_2") (pintype "passive"))
      (node (ref "R25") (pin "2") (pinfunction "right_2") (pintype "passive"))
    )
    (net (code "79") (name "Net-(LED26-K)") (class "Default")
      (node (ref "LED26") (pin "2") (pinfunction "K_2") (pintype "passive"))
      (node (ref "R26") (pin "2") (pinfunction "right_2") (pintype "passive"))
    )
    (net (code "80") (name "Net-(LED27-K)") (class "Default")
      (node (ref "LED27") (pin "2") (pinfunction "K_2") (pintype "passive"))
      (node (ref "R27") (pin "2") (pinfunction "right_2") (pintype "passive"))
    )
    (net (code "81") (name "Net-(LED28-K)") (class "Default")
      (node (ref "LED28") (pin "2") (pinfunction "K_2") (pintype "passive"))
      (node (ref "R28") (pin "2") (pinfunction "right_2") (pintype "passive"))
    )
    (net (code "82") (name "Net-(LED29-K)") (class "Default")
      (node (ref "LED29") (pin "2") (pinfunction "K_2") (pintype "passive"))
      (node (ref "R29") (pin "2") (pinfunction "right_2") (pintype "passive"))
    )
    (net (code "83") (name "Net-(LED30-K)") (class "Default")
      (node (ref "LED30") (pin "2") (pinfunction "K_2") (pintype "passive"))
      (node (ref "R30") (pin "2") (pinfunction "right_2") (pintype "passive"))
    )
    (net (code "84") (name "Net-(LED31-K)") (class "Default")
      (node (ref "LED31") (pin "2") (pinfunction "K_2") (pintype "passive"))
      (node (ref "R31") (pin "2") (pinfunction "right_2") (pintype "passive"))
    )
    (net (code "85") (name "Net-(LED32-K)") (class "Default")
      (node (ref "LED32") (pin "2") (pinfunction "K_2") (pintype "passive"))
      (node (ref "R32") (pin "2") (pinfunction "right_2") (pintype "passive"))
    )
    (net (code "86") (name "Net-(LED33-K)") (class "Default")
      (node (ref "LED33") (pin "2") (pinfunction "K_2") (pintype "passive"))
      (node (ref "R42") (pin "2") (pinfunction "right_2") (pintype "passive"))
    )
    (net (code "87") (name "Net-(LED34-K)") (class "Default")
      (node (ref "LED34") (pin "2") (pinfunction "K_2") (pintype "passive"))
      (node (ref "R50") (pin "2") (pinfunction "right_2") (pintype "passive"))
    )
    (net (code "88") (name "Net-(R34-right)") (class "Default")
      (node (ref "R34") (pin "2") (pinfunction "right_2") (pintype "passive"))
      (node (ref "R37") (pin "1") (pinfunction "left_1") (pintype "passive"))
      (node (ref "R38") (pin "2") (pinfunction "right_2") (pintype "passive"))
    )
    (net (code "89") (name "Net-(R35-right)") (class "Default")
      (node (ref "R35") (pin "2") (pinfunction "right_2") (pintype "passive"))
      (node (ref "R38") (pin "1") (pinfunction "left_1") (pintype "passive"))
      (node (ref "R39") (pin "2") (pinfunction "right_2") (pintype "passive"))
    )
    (net (code "90") (name "Net-(R36-right)") (class "Default")
      (node (ref "R36") (pin "2") (pinfunction "right_2") (pintype "passive"))
      (node (ref "R39") (pin "1") (pinfunction "left_1") (pintype "passive"))
      (node (ref "R40") (pin "2") (pinfunction "right_2") (pintype "passive"))
    )
    (net (code "91") (name "Net-(R43-left)") (class "Default")
      (node (ref "R43") (pin "1") (pinfunction "left_1") (pintype "passive"))
      (node (ref "T1") (pin "1") (pinfunction "1_1") (pintype "passive"))
    )
    (net (code "92") (name "Net-(R45-right)") (class "Default")
      (node (ref "R45") (pin "2") (pinfunction "right_2") (pintype "passive"))
      (node (ref "X1") (pin "2") (pinfunction "2_2") (pintype "passive"))
    )
    (net (code "93") (name "Net-(R46-right)") (class "Default")
      (node (ref "R46") (pin "2") (pinfunction "right_2") (pintype "passive"))
      (node (ref "X1") (pin "3") (pinfunction "3_3") (pintype "passive"))
    )
    (net (code "94") (name "Net-(R47-right)") (class "Default")
      (node (ref "R47") (pin "2") (pinfunction "right_2") (pintype "passive"))
      (node (ref "X1") (pin "4") (pinfunction "4_4") (pintype "passive"))
    )
    (net (code "95") (name "VCC") (class "Default")
      (node (ref "C1") (pin "1") (pinfunction "+_1") (pintype "passive"))
      (node (ref "C2") (pin "1") (pinfunction "+_1") (pintype "passive"))
      (node (ref "C3") (pin "1") (pinfunction "+_1") (pintype "passive"))
      (node (ref "C4") (pin "1") (pinfunction "+_1") (pintype "passive"))
      (node (ref "C5") (pin "1") (pinfunction "+_1") (pintype "passive"))
      (node (ref "C6") (pin "1") (pinfunction "+_1") (pintype "passive"))
      (node (ref "C7") (pin "1") (pinfunction "+_1") (pintype "passive"))
      (node (ref "C8") (pin "1") (pinfunction "+_1") (pintype "passive"))
      (node (ref "IC1") (pin "3") (pinfunction "IN_3") (pintype "passive"))
      (node (ref "IC2") (pin "10") (pinfunction "MR_10") (pintype "passive"))
      (node (ref "IC2") (pin "16") (pinfunction "VCC_16") (pintype "passive"))
      (node (ref "IC3") (pin "10") (pinfunction "MR_10") (pintype "passive"))
      (node (ref "IC3") (pin "16") (pinfunction "VCC_16") (pintype "passive"))
      (node (ref "IC4") (pin "10") (pinfunction "MR_10") (pintype "passive"))
      (node (ref "IC4") (pin "16") (pinfunction "VCC_16") (pintype "passive"))
      (node (ref "IC5") (pin "10") (pinfunction "MR_10") (pintype "passive"))
      (node (ref "IC5") (pin "16") (pinfunction "VCC_16") (pintype "passive"))
      (node (ref "IC6") (pin "16") (pinfunction "VCC_16") (pintype "passive"))
      (node (ref "LED33") (pin "1") (pinfunction "А_1") (pintype "passive"))
      (node (ref "R44") (pin "1") (pinfunction "left_1") (pintype "passive"))
      (node (ref "R48") (pin "1") (pinfunction "left_1") (pintype "passive"))
      (node (ref "X1") (pin "1") (pinfunction "1_1") (pintype "passive"))
    )
    (net (code "96") (name "unconnected-(H1-Pad1)") (class "Default")
      (node (ref "H1") (pin "1") (pinfunction "1_1") (pintype "passive"))
    )
    (net (code "97") (name "unconnected-(H2-Pad1)") (class "Default")
      (node (ref "H2") (pin "1") (pinfunction "1_1") (pintype "passive"))
    )
    (net (code "98") (name "unconnected-(H3-Pad1)") (class "Default")
      (node (ref "H3") (pin "1") (pinfunction "1_1") (pintype "passive"))
    )
    (net (code "99") (name "unconnected-(H4-Pad1)") (class "Default")
      (node (ref "H4") (pin "1") (pinfunction "1_1") (pintype "passive"))
    )
    (net (code "100") (name "unconnected-(IC6-!Q7-Pad9)") (class "Default")
      (node (ref "IC6") (pin "9") (pinfunction "!Q7_9") (pintype "passive"))
    )
    (net (code "101") (name "unconnected-(IC6-Q4-Pad4)") (class "Default")
      (node (ref "IC6") (pin "4") (pinfunction "Q4_4") (pintype "passive"))
    )
    (net (code "102") (name "unconnected-(IC6-Q5-Pad5)") (class "Default")
      (node (ref "IC6") (pin "5") (pinfunction "Q5_5") (pintype "passive"))
    )
    (net (code "103") (name "unconnected-(IC6-Q6-Pad6)") (class "Default")
      (node (ref "IC6") (pin "6") (pinfunction "Q6_6") (pintype "passive"))
    )
  )
)
